# flash.net
KiCad netlist of a schematic drawn in Altium Designer
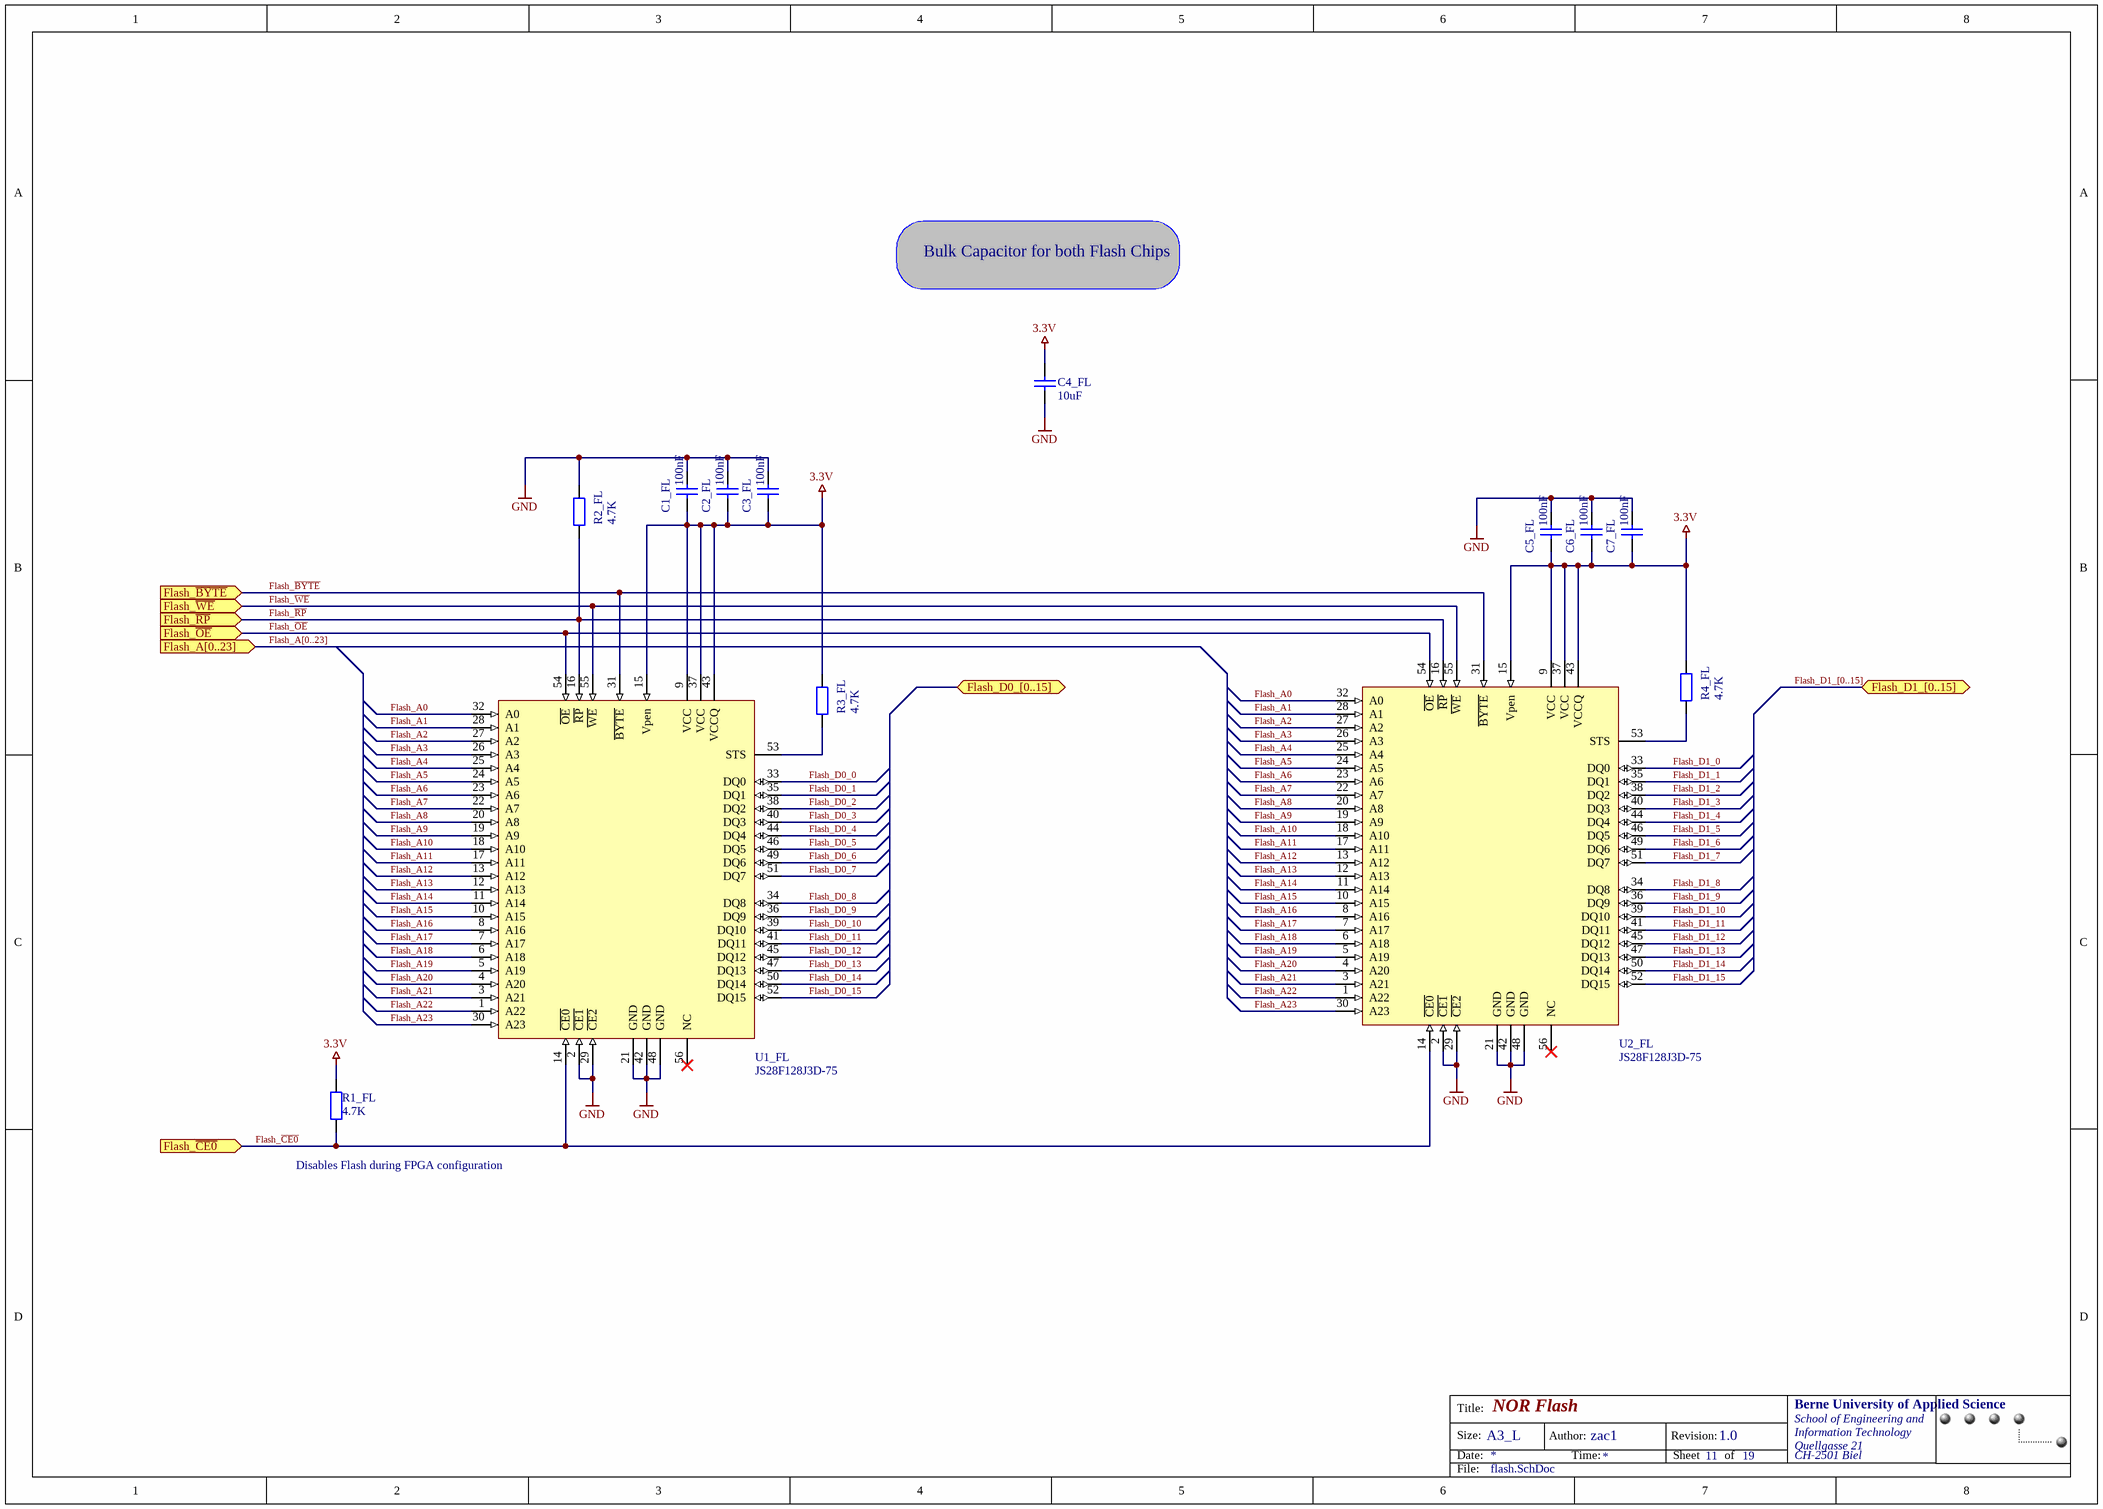
[diagram p0: flash.SchDoc]

(export (version "E")
  (design (tool "Eeschema 10.0.6"))
  (components
    (comp (ref "C1_FL")
      (value "100nF")
      (footprint "0402")
      (description "Capacitor")
      (fields
        (field (name "MANUFACTURER") "Murata")
        (field (name "PART NUMBER") "GRM155R71C104KA88D")
        (field (name "PUBLISHER") "Altium Limited")
      )
      (libsource (lib "Miscellaneous Devices") (part "Cap"))
    )
    (comp (ref "C2_FL")
      (value "100nF")
      (footprint "0402")
      (description "Capacitor")
      (fields
        (field (name "MANUFACTURER") "Murata")
        (field (name "PART NUMBER") "GRM155R71C104KA88D")
        (field (name "PUBLISHER") "Altium Limited")
      )
      (libsource (lib "Miscellaneous Devices") (part "Cap"))
    )
    (comp (ref "C3_FL")
      (value "100nF")
      (footprint "0402")
      (description "Capacitor")
      (fields
        (field (name "MANUFACTURER") "Murata")
        (field (name "PART NUMBER") "GRM155R71C104KA88D")
        (field (name "PUBLISHER") "Altium Limited")
      )
      (libsource (lib "Miscellaneous Devices") (part "Cap"))
    )
    (comp (ref "C4_FL")
      (value "10uF")
      (footprint "1206")
      (description "Capacitor")
      (fields
        (field (name "MANUFACTURER") "Murata")
        (field (name "PART NUMBER") "GRM31CR70J106KA01L")
        (field (name "PUBLISHER") "Altium Limited")
      )
      (libsource (lib "Miscellaneous Devices") (part "Cap"))
    )
    (comp (ref "C5_FL")
      (value "100nF")
      (footprint "0402")
      (description "Capacitor")
      (fields
        (field (name "MANUFACTURER") "Murata")
        (field (name "PART NUMBER") "GRM155R71C104KA88D")
        (field (name "PUBLISHER") "Altium Limited")
      )
      (libsource (lib "Miscellaneous Devices") (part "Cap"))
    )
    (comp (ref "C6_FL")
      (value "100nF")
      (footprint "0402")
      (description "Capacitor")
      (fields
        (field (name "MANUFACTURER") "Murata")
        (field (name "PART NUMBER") "GRM155R71C104KA88D")
        (field (name "PUBLISHER") "Altium Limited")
      )
      (libsource (lib "Miscellaneous Devices") (part "Cap"))
    )
    (comp (ref "C7_FL")
      (value "100nF")
      (footprint "0402")
      (description "Capacitor")
      (fields
        (field (name "MANUFACTURER") "Murata")
        (field (name "PART NUMBER") "GRM155R71C104KA88D")
        (field (name "PUBLISHER") "Altium Limited")
      )
      (libsource (lib "Miscellaneous Devices") (part "Cap"))
    )
    (comp (ref "R1_FL")
      (value "4.7K")
      (footprint "0402")
      (description "Resistor")
      (fields
        (field (name "MANUFACTURER") "PHYCOMP")
        (field (name "PART NUMBER") "232270674702")
        (field (name "PUBLISHER") "Altium Limited")
      )
      (libsource (lib "") (part "Res2_1"))
    )
    (comp (ref "R2_FL")
      (value "4.7K")
      (footprint "0402")
      (description "Resistor")
      (fields
        (field (name "MANUFACTURER") "PHYCOMP")
        (field (name "PART NUMBER") "232270674702")
        (field (name "PUBLISHER") "Altium Limited")
      )
      (libsource (lib "Miscellaneous Devices") (part "Res2"))
    )
    (comp (ref "R3_FL")
      (value "4.7K")
      (footprint "0402")
      (description "Resistor")
      (fields
        (field (name "MANUFACTURER") "PHYCOMP")
        (field (name "PART NUMBER") "232270674702")
        (field (name "PUBLISHER") "Altium Limited")
      )
      (libsource (lib "Miscellaneous Devices") (part "Res2"))
    )
    (comp (ref "R4_FL")
      (value "4.7K")
      (footprint "0402")
      (description "Resistor")
      (fields
        (field (name "MANUFACTURER") "PHYCOMP")
        (field (name "PART NUMBER") "232270674702")
        (field (name "PUBLISHER") "Altium Limited")
      )
      (libsource (lib "Miscellaneous Devices") (part "Res2"))
    )
    (comp (ref "U1_FL")
      (value "JS28F128J3D-75")
      (footprint "TSSO14X20-G56")
      (description "Intel embedded Flash J3")
      (fields (field (name "MANUFACTURER") "Intel") (field (name "Comment") "JS28FXXXJ3D-75"))
      (libsource (lib "gecko3-user") (part "JS28FXXXJ3D-75"))
    )
    (comp (ref "U2_FL")
      (value "JS28F128J3D-75")
      (footprint "TSSO14X20-G56")
      (description "Intel embedded Flash J3")
      (fields (field (name "MANUFACTURER") "Intel") (field (name "Comment") "JS28FXXXJ3D-75"))
      (libsource (lib "gecko3-user") (part "JS28FXXXJ3D-75"))
    )
  )
  (nets
    (net (code "1") (name "/Flash_A0") (class "Default")
      (node (ref "U1_FL") (pin "32") (pinfunction "A0_32") (pintype "input"))
      (node (ref "U2_FL") (pin "32") (pinfunction "A0_32") (pintype "input"))
    )
    (net (code "2") (name "/Flash_A1") (class "Default")
      (node (ref "U1_FL") (pin "28") (pinfunction "A1_28") (pintype "input"))
      (node (ref "U2_FL") (pin "28") (pinfunction "A1_28") (pintype "input"))
    )
    (net (code "3") (name "/Flash_A2") (class "Default")
      (node (ref "U1_FL") (pin "27") (pinfunction "A2_27") (pintype "input"))
      (node (ref "U2_FL") (pin "27") (pinfunction "A2_27") (pintype "input"))
    )
    (net (code "4") (name "/Flash_A3") (class "Default")
      (node (ref "U1_FL") (pin "26") (pinfunction "A3_26") (pintype "input"))
      (node (ref "U2_FL") (pin "26") (pinfunction "A3_26") (pintype "input"))
    )
    (net (code "5") (name "/Flash_A4") (class "Default")
      (node (ref "U1_FL") (pin "25") (pinfunction "A4_25") (pintype "input"))
      (node (ref "U2_FL") (pin "25") (pinfunction "A4_25") (pintype "input"))
    )
    (net (code "6") (name "/Flash_A5") (class "Default")
      (node (ref "U1_FL") (pin "24") (pinfunction "A5_24") (pintype "input"))
      (node (ref "U2_FL") (pin "24") (pinfunction "A5_24") (pintype "input"))
    )
    (net (code "7") (name "/Flash_A6") (class "Default")
      (node (ref "U1_FL") (pin "23") (pinfunction "A6_23") (pintype "input"))
      (node (ref "U2_FL") (pin "23") (pinfunction "A6_23") (pintype "input"))
    )
    (net (code "8") (name "/Flash_A7") (class "Default")
      (node (ref "U1_FL") (pin "22") (pinfunction "A7_22") (pintype "input"))
      (node (ref "U2_FL") (pin "22") (pinfunction "A7_22") (pintype "input"))
    )
    (net (code "9") (name "/Flash_A8") (class "Default")
      (node (ref "U1_FL") (pin "20") (pinfunction "A8_20") (pintype "input"))
      (node (ref "U2_FL") (pin "20") (pinfunction "A8_20") (pintype "input"))
    )
    (net (code "10") (name "/Flash_A9") (class "Default")
      (node (ref "U1_FL") (pin "19") (pinfunction "A9_19") (pintype "input"))
      (node (ref "U2_FL") (pin "19") (pinfunction "A9_19") (pintype "input"))
    )
    (net (code "11") (name "/Flash_A10") (class "Default")
      (node (ref "U1_FL") (pin "18") (pinfunction "A10_18") (pintype "input"))
      (node (ref "U2_FL") (pin "18") (pinfunction "A10_18") (pintype "input"))
    )
    (net (code "12") (name "/Flash_A11") (class "Default")
      (node (ref "U1_FL") (pin "17") (pinfunction "A11_17") (pintype "input"))
      (node (ref "U2_FL") (pin "17") (pinfunction "A11_17") (pintype "input"))
    )
    (net (code "13") (name "/Flash_A12") (class "Default")
      (node (ref "U1_FL") (pin "13") (pinfunction "A12_13") (pintype "input"))
      (node (ref "U2_FL") (pin "13") (pinfunction "A12_13") (pintype "input"))
    )
    (net (code "14") (name "/Flash_A13") (class "Default")
      (node (ref "U1_FL") (pin "12") (pinfunction "A13_12") (pintype "input"))
      (node (ref "U2_FL") (pin "12") (pinfunction "A13_12") (pintype "input"))
    )
    (net (code "15") (name "/Flash_A14") (class "Default")
      (node (ref "U1_FL") (pin "11") (pinfunction "A14_11") (pintype "input"))
      (node (ref "U2_FL") (pin "11") (pinfunction "A14_11") (pintype "input"))
    )
    (net (code "16") (name "/Flash_A15") (class "Default")
      (node (ref "U1_FL") (pin "10") (pinfunction "A15_10") (pintype "input"))
      (node (ref "U2_FL") (pin "10") (pinfunction "A15_10") (pintype "input"))
    )
    (net (code "17") (name "/Flash_A16") (class "Default")
      (node (ref "U1_FL") (pin "8") (pinfunction "A16_8") (pintype "input"))
      (node (ref "U2_FL") (pin "8") (pinfunction "A16_8") (pintype "input"))
    )
    (net (code "18") (name "/Flash_A17") (class "Default")
      (node (ref "U1_FL") (pin "7") (pinfunction "A17_7") (pintype "input"))
      (node (ref "U2_FL") (pin "7") (pinfunction "A17_7") (pintype "input"))
    )
    (net (code "19") (name "/Flash_A18") (class "Default")
      (node (ref "U1_FL") (pin "6") (pinfunction "A18_6") (pintype "input"))
      (node (ref "U2_FL") (pin "6") (pinfunction "A18_6") (pintype "input"))
    )
    (net (code "20") (name "/Flash_A19") (class "Default")
      (node (ref "U1_FL") (pin "5") (pinfunction "A19_5") (pintype "input"))
      (node (ref "U2_FL") (pin "5") (pinfunction "A19_5") (pintype "input"))
    )
    (net (code "21") (name "/Flash_A20") (class "Default")
      (node (ref "U1_FL") (pin "4") (pinfunction "A20_4") (pintype "input"))
      (node (ref "U2_FL") (pin "4") (pinfunction "A20_4") (pintype "input"))
    )
    (net (code "22") (name "/Flash_A21") (class "Default")
      (node (ref "U1_FL") (pin "3") (pinfunction "A21_3") (pintype "input"))
      (node (ref "U2_FL") (pin "3") (pinfunction "A21_3") (pintype "input"))
    )
    (net (code "23") (name "/Flash_A22") (class "Default")
      (node (ref "U1_FL") (pin "1") (pinfunction "A22_1") (pintype "input"))
      (node (ref "U2_FL") (pin "1") (pinfunction "A22_1") (pintype "input"))
    )
    (net (code "24") (name "/Flash_A23") (class "Default")
      (node (ref "U1_FL") (pin "30") (pinfunction "A23_30") (pintype "input"))
      (node (ref "U2_FL") (pin "30") (pinfunction "A23_30") (pintype "input"))
    )
    (net (code "26") (name "/Flash_D0_0") (class "Default")
      (node (ref "U1_FL") (pin "33") (pinfunction "DQ0_33") (pintype "bidirectional"))
    )
    (net (code "27") (name "/Flash_D0_1") (class "Default")
      (node (ref "U1_FL") (pin "35") (pinfunction "DQ1_35") (pintype "bidirectional"))
    )
    (net (code "28") (name "/Flash_D0_2") (class "Default")
      (node (ref "U1_FL") (pin "38") (pinfunction "DQ2_38") (pintype "bidirectional"))
    )
    (net (code "29") (name "/Flash_D0_3") (class "Default")
      (node (ref "U1_FL") (pin "40") (pinfunction "DQ3_40") (pintype "bidirectional"))
    )
    (net (code "30") (name "/Flash_D0_4") (class "Default")
      (node (ref "U1_FL") (pin "44") (pinfunction "DQ4_44") (pintype "bidirectional"))
    )
    (net (code "31") (name "/Flash_D0_5") (class "Default")
      (node (ref "U1_FL") (pin "46") (pinfunction "DQ5_46") (pintype "bidirectional"))
    )
    (net (code "32") (name "/Flash_D0_6") (class "Default")
      (node (ref "U1_FL") (pin "49") (pinfunction "DQ6_49") (pintype "bidirectional"))
    )
    (net (code "33") (name "/Flash_D0_7") (class "Default")
      (node (ref "U1_FL") (pin "51") (pinfunction "DQ7_51") (pintype "bidirectional"))
    )
    (net (code "34") (name "/Flash_D0_8") (class "Default")
      (node (ref "U1_FL") (pin "34") (pinfunction "DQ8_34") (pintype "bidirectional"))
    )
    (net (code "35") (name "/Flash_D0_9") (class "Default")
      (node (ref "U1_FL") (pin "36") (pinfunction "DQ9_36") (pintype "bidirectional"))
    )
    (net (code "36") (name "/Flash_D0_10") (class "Default")
      (node (ref "U1_FL") (pin "39") (pinfunction "DQ10_39") (pintype "bidirectional"))
    )
    (net (code "37") (name "/Flash_D0_11") (class "Default")
      (node (ref "U1_FL") (pin "41") (pinfunction "DQ11_41") (pintype "bidirectional"))
    )
    (net (code "38") (name "/Flash_D0_12") (class "Default")
      (node (ref "U1_FL") (pin "45") (pinfunction "DQ12_45") (pintype "bidirectional"))
    )
    (net (code "39") (name "/Flash_D0_13") (class "Default")
      (node (ref "U1_FL") (pin "47") (pinfunction "DQ13_47") (pintype "bidirectional"))
    )
    (net (code "40") (name "/Flash_D0_14") (class "Default")
      (node (ref "U1_FL") (pin "50") (pinfunction "DQ14_50") (pintype "bidirectional"))
    )
    (net (code "41") (name "/Flash_D0_15") (class "Default")
      (node (ref "U1_FL") (pin "52") (pinfunction "DQ15_52") (pintype "bidirectional"))
    )
    (net (code "43") (name "/Flash_D1_0") (class "Default")
      (node (ref "U2_FL") (pin "33") (pinfunction "DQ0_33") (pintype "bidirectional"))
    )
    (net (code "44") (name "/Flash_D1_1") (class "Default")
      (node (ref "U2_FL") (pin "35") (pinfunction "DQ1_35") (pintype "bidirectional"))
    )
    (net (code "45") (name "/Flash_D1_2") (class "Default")
      (node (ref "U2_FL") (pin "38") (pinfunction "DQ2_38") (pintype "bidirectional"))
    )
    (net (code "46") (name "/Flash_D1_3") (class "Default")
      (node (ref "U2_FL") (pin "40") (pinfunction "DQ3_40") (pintype "bidirectional"))
    )
    (net (code "47") (name "/Flash_D1_4") (class "Default")
      (node (ref "U2_FL") (pin "44") (pinfunction "DQ4_44") (pintype "bidirectional"))
    )
    (net (code "48") (name "/Flash_D1_5") (class "Default")
      (node (ref "U2_FL") (pin "46") (pinfunction "DQ5_46") (pintype "bidirectional"))
    )
    (net (code "49") (name "/Flash_D1_6") (class "Default")
      (node (ref "U2_FL") (pin "49") (pinfunction "DQ6_49") (pintype "bidirectional"))
    )
    (net (code "50") (name "/Flash_D1_7") (class "Default")
      (node (ref "U2_FL") (pin "51") (pinfunction "DQ7_51") (pintype "bidirectional"))
    )
    (net (code "51") (name "/Flash_D1_8") (class "Default")
      (node (ref "U2_FL") (pin "34") (pinfunction "DQ8_34") (pintype "bidirectional"))
    )
    (net (code "52") (name "/Flash_D1_9") (class "Default")
      (node (ref "U2_FL") (pin "36") (pinfunction "DQ9_36") (pintype "bidirectional"))
    )
    (net (code "53") (name "/Flash_D1_10") (class "Default")
      (node (ref "U2_FL") (pin "39") (pinfunction "DQ10_39") (pintype "bidirectional"))
    )
    (net (code "54") (name "/Flash_D1_11") (class "Default")
      (node (ref "U2_FL") (pin "41") (pinfunction "DQ11_41") (pintype "bidirectional"))
    )
    (net (code "55") (name "/Flash_D1_12") (class "Default")
      (node (ref "U2_FL") (pin "45") (pinfunction "DQ12_45") (pintype "bidirectional"))
    )
    (net (code "56") (name "/Flash_D1_13") (class "Default")
      (node (ref "U2_FL") (pin "47") (pinfunction "DQ13_47") (pintype "bidirectional"))
    )
    (net (code "57") (name "/Flash_D1_14") (class "Default")
      (node (ref "U2_FL") (pin "50") (pinfunction "DQ14_50") (pintype "bidirectional"))
    )
    (net (code "58") (name "/Flash_D1_15") (class "Default")
      (node (ref "U2_FL") (pin "52") (pinfunction "DQ15_52") (pintype "bidirectional"))
    )
    (net (code "60") (name "/Flash_~{BYTE}") (class "Default")
      (node (ref "U1_FL") (pin "31") (pinfunction "~{BYTE}_31") (pintype "input"))
      (node (ref "U2_FL") (pin "31") (pinfunction "~{BYTE}_31") (pintype "input"))
    )
    (net (code "61") (name "/Flash_~{CE0}") (class "Default")
      (node (ref "R1_FL") (pin "2") (pinfunction "2_2") (pintype "passive"))
      (node (ref "U1_FL") (pin "14") (pinfunction "~{CE0}_14") (pintype "input"))
      (node (ref "U2_FL") (pin "14") (pinfunction "~{CE0}_14") (pintype "input"))
    )
    (net (code "62") (name "/Flash_~{OE}") (class "Default")
      (node (ref "U1_FL") (pin "54") (pinfunction "~{OE}_54") (pintype "input"))
      (node (ref "U2_FL") (pin "54") (pinfunction "~{OE}_54") (pintype "input"))
    )
    (net (code "63") (name "/Flash_~{RP}") (class "Default")
      (node (ref "R2_FL") (pin "1") (pinfunction "1_1") (pintype "passive"))
      (node (ref "U1_FL") (pin "16") (pinfunction "~{RP}_16") (pintype "input"))
      (node (ref "U2_FL") (pin "16") (pinfunction "~{RP}_16") (pintype "input"))
    )
    (net (code "64") (name "/Flash_~{WE}") (class "Default")
      (node (ref "U1_FL") (pin "55") (pinfunction "~{WE}_55") (pintype "input"))
      (node (ref "U2_FL") (pin "55") (pinfunction "~{WE}_55") (pintype "input"))
    )
    (net (code "65") (name "3.3V") (class "Default")
      (node (ref "C1_FL") (pin "2") (pinfunction "2_2") (pintype "passive"))
      (node (ref "C2_FL") (pin "2") (pinfunction "2_2") (pintype "passive"))
      (node (ref "C3_FL") (pin "2") (pinfunction "2_2") (pintype "passive"))
      (node (ref "C4_FL") (pin "2") (pinfunction "2_2") (pintype "passive"))
      (node (ref "C5_FL") (pin "2") (pinfunction "2_2") (pintype "passive"))
      (node (ref "C6_FL") (pin "2") (pinfunction "2_2") (pintype "passive"))
      (node (ref "C7_FL") (pin "2") (pinfunction "2_2") (pintype "passive"))
      (node (ref "R1_FL") (pin "1") (pinfunction "1_1") (pintype "passive"))
      (node (ref "R3_FL") (pin "2") (pinfunction "2_2") (pintype "passive"))
      (node (ref "R4_FL") (pin "2") (pinfunction "2_2") (pintype "passive"))
      (node (ref "U1_FL") (pin "15") (pinfunction "Vpen_15") (pintype "input"))
      (node (ref "U1_FL") (pin "37") (pinfunction "VCC_37") (pintype "power_in"))
      (node (ref "U1_FL") (pin "43") (pinfunction "VCCQ_43") (pintype "power_in"))
      (node (ref "U1_FL") (pin "9") (pinfunction "VCC_9") (pintype "power_in"))
      (node (ref "U2_FL") (pin "15") (pinfunction "Vpen_15") (pintype "input"))
      (node (ref "U2_FL") (pin "37") (pinfunction "VCC_37") (pintype "power_in"))
      (node (ref "U2_FL") (pin "43") (pinfunction "VCCQ_43") (pintype "power_in"))
      (node (ref "U2_FL") (pin "9") (pinfunction "VCC_9") (pintype "power_in"))
    )
    (net (code "66") (name "GND") (class "Default")
      (node (ref "C1_FL") (pin "1") (pinfunction "1_1") (pintype "passive"))
      (node (ref "C2_FL") (pin "1") (pinfunction "1_1") (pintype "passive"))
      (node (ref "C3_FL") (pin "1") (pinfunction "1_1") (pintype "passive"))
      (node (ref "C4_FL") (pin "1") (pinfunction "1_1") (pintype "passive"))
      (node (ref "C5_FL") (pin "1") (pinfunction "1_1") (pintype "passive"))
      (node (ref "C6_FL") (pin "1") (pinfunction "1_1") (pintype "passive"))
      (node (ref "C7_FL") (pin "1") (pinfunction "1_1") (pintype "passive"))
      (node (ref "R2_FL") (pin "2") (pinfunction "2_2") (pintype "passive"))
      (node (ref "U1_FL") (pin "2") (pinfunction "~{CE1}_2") (pintype "input"))
      (node (ref "U1_FL") (pin "21") (pinfunction "GND_21") (pintype "power_in"))
      (node (ref "U1_FL") (pin "29") (pinfunction "~{CE2}_29") (pintype "input"))
      (node (ref "U1_FL") (pin "42") (pinfunction "GND_42") (pintype "power_in"))
      (node (ref "U1_FL") (pin "48") (pinfunction "GND_48") (pintype "power_in"))
      (node (ref "U2_FL") (pin "2") (pinfunction "~{CE1}_2") (pintype "input"))
      (node (ref "U2_FL") (pin "21") (pinfunction "GND_21") (pintype "power_in"))
      (node (ref "U2_FL") (pin "29") (pinfunction "~{CE2}_29") (pintype "input"))
      (node (ref "U2_FL") (pin "42") (pinfunction "GND_42") (pintype "power_in"))
      (node (ref "U2_FL") (pin "48") (pinfunction "GND_48") (pintype "power_in"))
    )
    (net (code "67") (name "Net-(U1_FL-STS)") (class "Default")
      (node (ref "R3_FL") (pin "1") (pinfunction "1_1") (pintype "passive"))
      (node (ref "U1_FL") (pin "53") (pinfunction "STS_53") (pintype "open_collector"))
    )
    (net (code "68") (name "Net-(U2_FL-STS)") (class "Default")
      (node (ref "R4_FL") (pin "1") (pinfunction "1_1") (pintype "passive"))
      (node (ref "U2_FL") (pin "53") (pinfunction "STS_53") (pintype "open_collector"))
    )
    (net (code "69") (name "unconnected-(U1_FL-NC-Pad56)") (class "Default")
      (node (ref "U1_FL") (pin "56") (pinfunction "NC_56") (pintype "passive+no_connect"))
    )
    (net (code "70") (name "unconnected-(U2_FL-NC-Pad56)") (class "Default")
      (node (ref "U2_FL") (pin "56") (pinfunction "NC_56") (pintype "passive+no_connect"))
    )
  )
)
